# USB-I2C_A2.net
KiCad netlist of a schematic drawn in Altium Designer
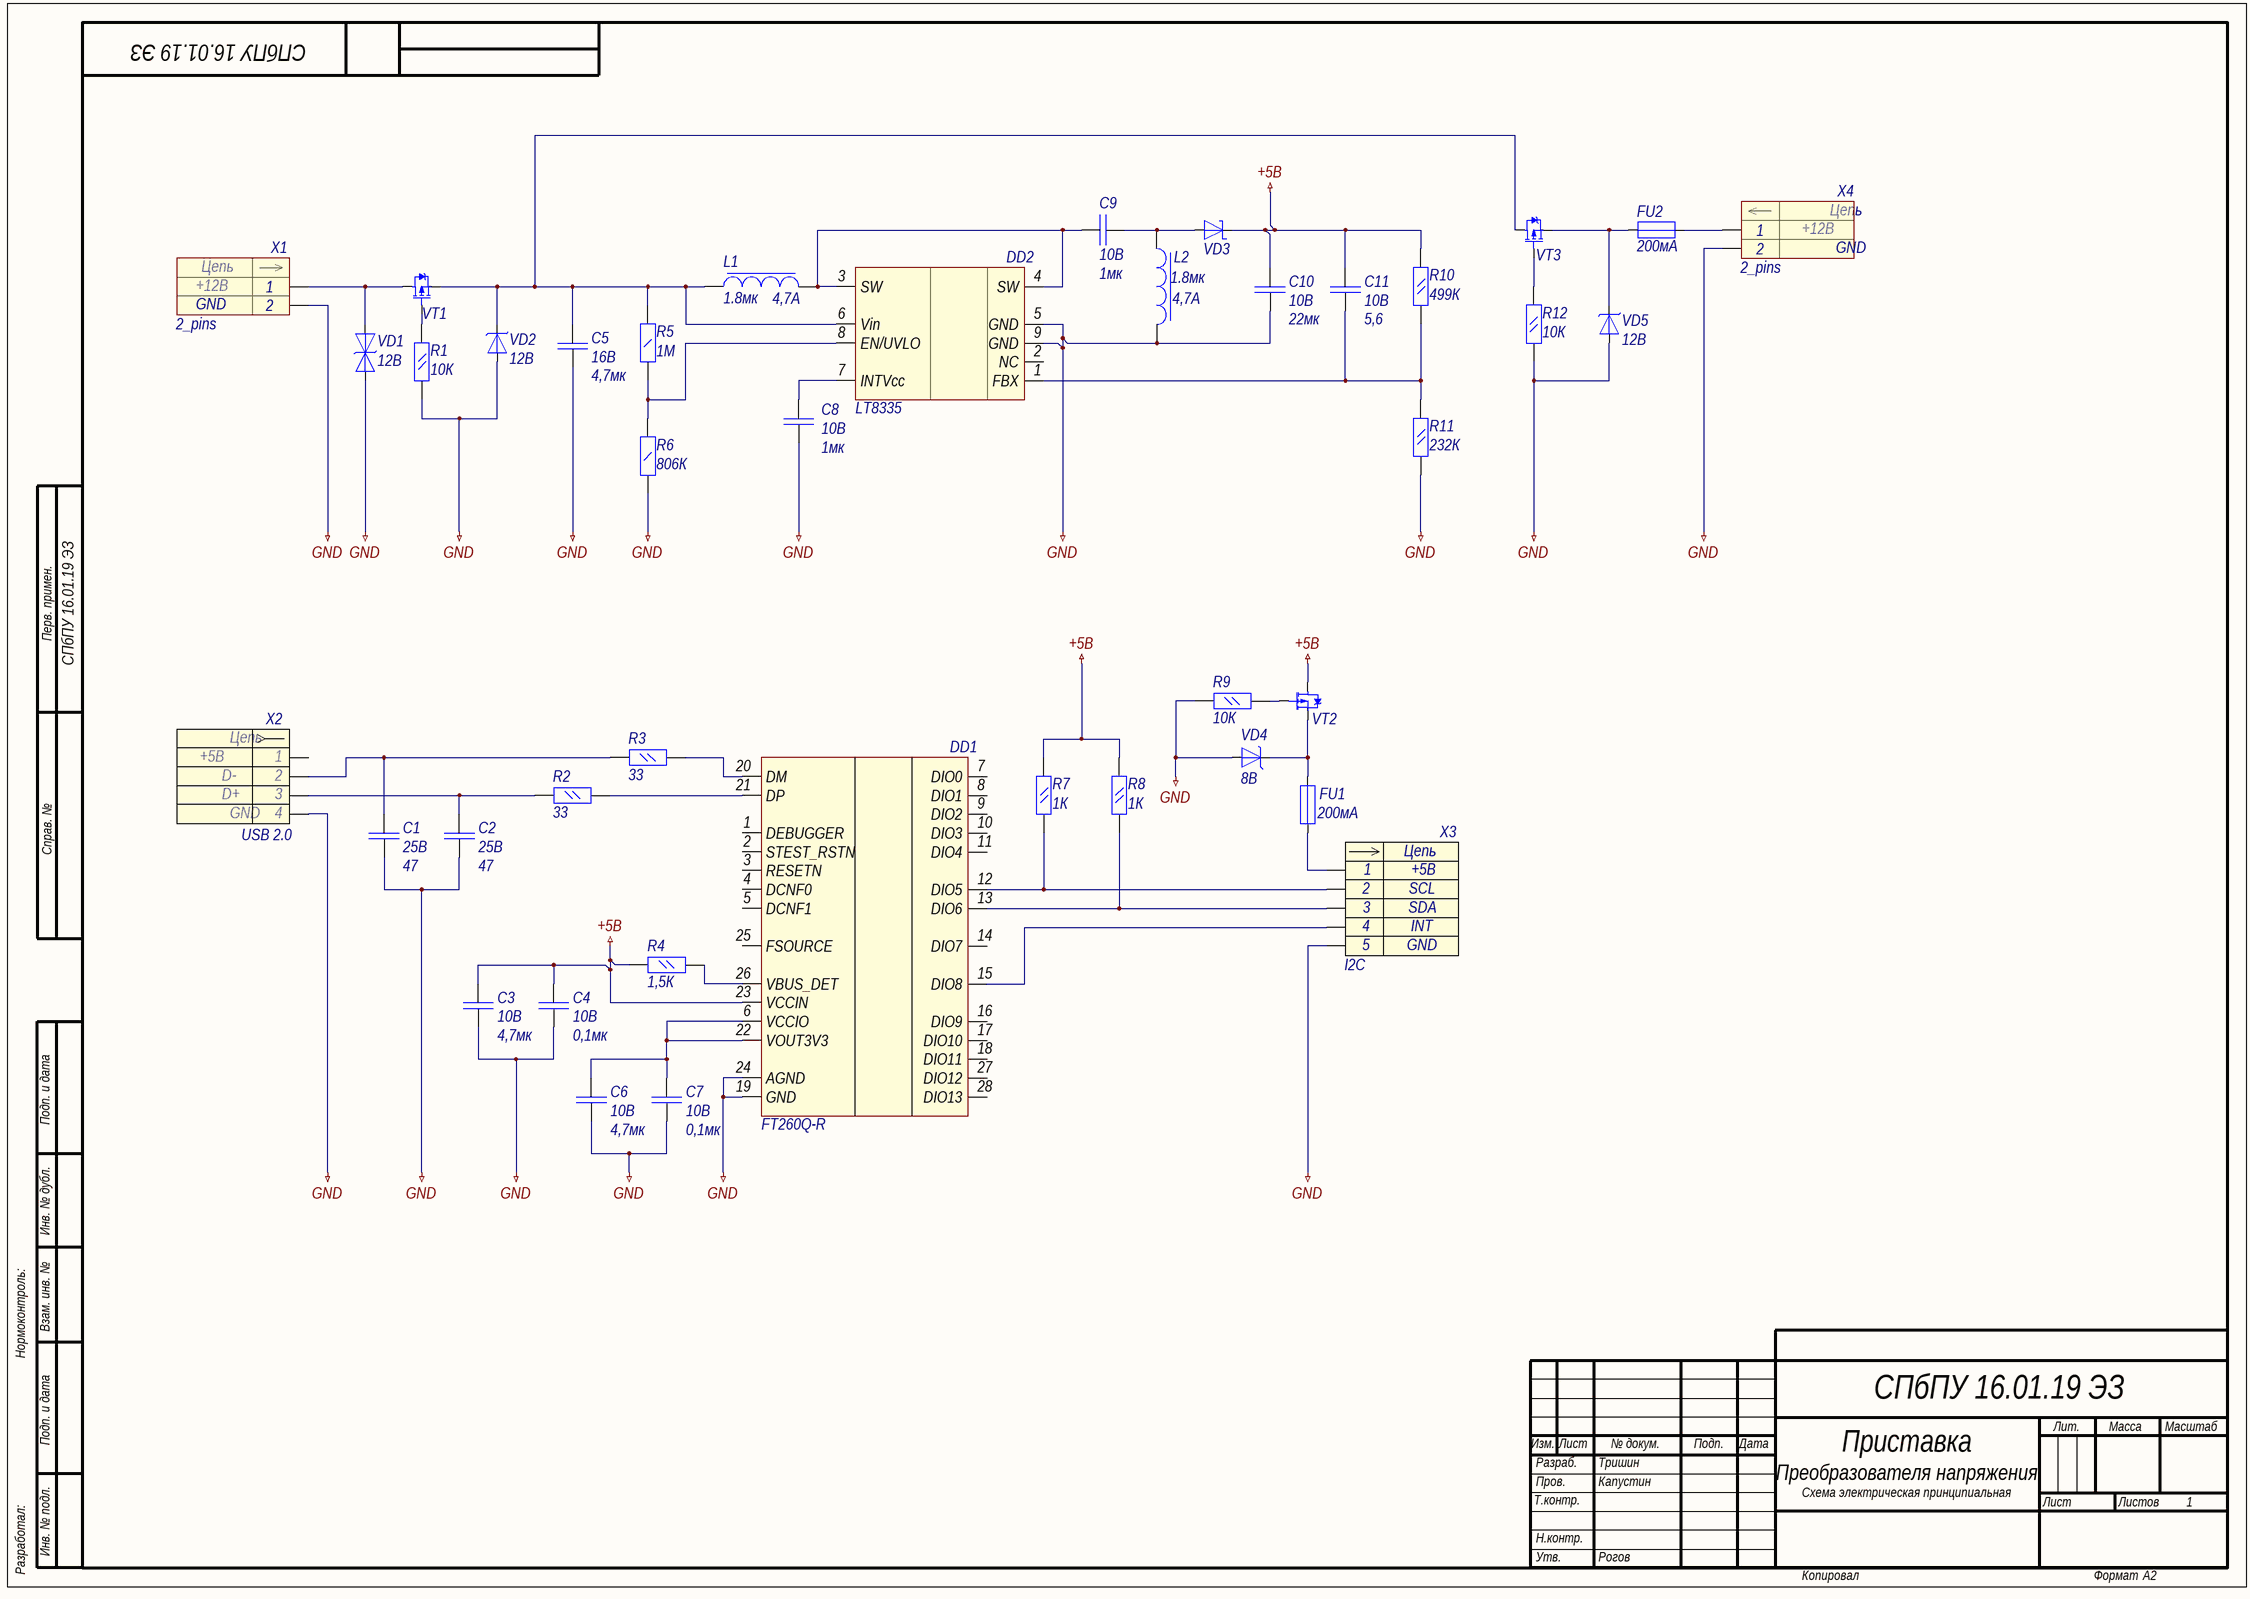
[diagram p0: USB-I2C_A2.SchDoc]

(export (version "E")
  (design (tool "Eeschema 10.0.6"))
  (components
    (comp (ref "C1")
      (value "Capacitor")
      (footprint "CH0201C")
      (fields (field (name "VOLTAGE") "25В") (field (name "CAPACITANCE") "47"))
      (libsource (lib "GOST_Capacitors") (part "Capacitor"))
    )
    (comp (ref "C2")
      (value "Capacitor")
      (footprint "CH0201C")
      (fields (field (name "VOLTAGE") "25В") (field (name "CAPACITANCE") "47"))
      (libsource (lib "GOST_Capacitors") (part "Capacitor"))
    )
    (comp (ref "C3")
      (value "Capacitor")
      (footprint "CH0402C")
      (fields (field (name "VOLTAGE") "10В") (field (name "CAPACITANCE") "4,7мк"))
      (libsource (lib "GOST_Capacitors") (part "Capacitor"))
    )
    (comp (ref "C4")
      (value "Capacitor")
      (footprint "CH0402C")
      (fields (field (name "VOLTAGE") "10В") (field (name "CAPACITANCE") "0,1мк"))
      (libsource (lib "GOST_Capacitors") (part "Capacitor"))
    )
    (comp (ref "C5")
      (value "Capacitor")
      (footprint "CH0603C")
      (fields (field (name "VOLTAGE") "16В") (field (name "CAPACITANCE") "4,7мк"))
      (libsource (lib "GOST_Capacitors") (part "Capacitor"))
    )
    (comp (ref "C6")
      (value "Capacitor")
      (footprint "CH0402C")
      (fields (field (name "VOLTAGE") "10В") (field (name "CAPACITANCE") "4,7мк"))
      (libsource (lib "GOST_Capacitors") (part "Capacitor"))
    )
    (comp (ref "C7")
      (value "Capacitor")
      (footprint "CH0402C")
      (fields (field (name "VOLTAGE") "10В") (field (name "CAPACITANCE") "0,1мк"))
      (libsource (lib "GOST_Capacitors") (part "Capacitor"))
    )
    (comp (ref "C8")
      (value "Capacitor")
      (footprint "CH0201C")
      (fields (field (name "VOLTAGE") "10В") (field (name "CAPACITANCE") "1мк"))
      (libsource (lib "GOST_Capacitors") (part "Capacitor"))
    )
    (comp (ref "C9")
      (value "Capacitor")
      (footprint "CH0201C")
      (fields (field (name "VOLTAGE") "10В") (field (name "CAPACITANCE") "1мк"))
      (libsource (lib "GOST_Capacitors") (part "Capacitor"))
    )
    (comp (ref "C10")
      (value "Capacitor")
      (footprint "CH0603C")
      (fields (field (name "VOLTAGE") "10В") (field (name "CAPACITANCE") "22мк"))
      (libsource (lib "GOST_Capacitors") (part "Capacitor"))
    )
    (comp (ref "C11")
      (value "Capacitor")
      (footprint "CH0201C")
      (fields (field (name "VOLTAGE") "10В") (field (name "CAPACITANCE") "5,6"))
      (libsource (lib "GOST_Capacitors") (part "Capacitor"))
    )
    (comp (ref "DD1")
      (value "FT260Q-R")
      (footprint "FT260-Q")
      (description "IC BRIDGE USB TO UART/I2C 28WQFN")
      (libsource (lib "GOST_lib_devices") (part "FT260Q-R"))
    )
    (comp (ref "DD2")
      (value "LT8335")
      (footprint "LT8335")
      (description "4~16 to 5")
      (libsource (lib "GOST_lib_devices") (part "LT8335"))
    )
    (comp (ref "FU1")
      (value "200мА")
      (footprint "CH0402R")
      (fields (field (name "Comment") "Fuse"))
      (libsource (lib "GOST_Miscelanuious") (part "Fuse"))
    )
    (comp (ref "FU2")
      (value "200мА")
      (footprint "CH0402R")
      (fields (field (name "Comment") "Fuse"))
      (libsource (lib "") (part "Fuse_1"))
    )
    (comp (ref "L1")
      (value "Ferrite bead")
      (footprint "IND: DRQ127")
      (fields (field (name "MAX DC CURRENT") "4,7А") (field (name "INDUCTANCE") "1.8мк"))
      (libsource (lib "GOST_Inductors") (part "Ferrite bead"))
    )
    (comp (ref "L2")
      (value "Ferrite bead")
      (footprint "IND: DRQ127")
      (fields (field (name "MAX DC CURRENT") "4,7А") (field (name "INDUCTANCE") "1.8мк"))
      (libsource (lib "GOST_Inductors") (part "Ferrite bead"))
    )
    (comp (ref "R1")
      (value "Res_0.125")
      (footprint "CH0402R")
      (fields (field (name "IMPEDANCE") "10К"))
      (libsource (lib "GOST_Resistors") (part "Res_0.125"))
    )
    (comp (ref "R2")
      (value "Res_0.125")
      (footprint "CH0402R")
      (fields (field (name "IMPEDANCE") "33"))
      (libsource (lib "GOST_Resistors") (part "Res_0.125"))
    )
    (comp (ref "R3")
      (value "Res_0.125")
      (footprint "CH0402R")
      (fields (field (name "IMPEDANCE") "33"))
      (libsource (lib "GOST_Resistors") (part "Res_0.125"))
    )
    (comp (ref "R4")
      (value "Res_0.125")
      (footprint "CH0402R")
      (fields (field (name "IMPEDANCE") "1,5К"))
      (libsource (lib "GOST_Resistors") (part "Res_0.125"))
    )
    (comp (ref "R5")
      (value "Res_0.5")
      (footprint "CH0805R")
      (fields (field (name "IMPEDANCE") "1М"))
      (libsource (lib "GOST_Resistors") (part "Res_0.5"))
    )
    (comp (ref "R6")
      (value "Res_0.5")
      (footprint "CH0805R")
      (fields (field (name "IMPEDANCE") "806К"))
      (libsource (lib "GOST_Resistors") (part "Res_0.5"))
    )
    (comp (ref "R7")
      (value "Res_0.125")
      (footprint "CH0402R")
      (fields (field (name "IMPEDANCE") "1К"))
      (libsource (lib "GOST_Resistors") (part "Res_0.125"))
    )
    (comp (ref "R8")
      (value "Res_0.125")
      (footprint "CH0402R")
      (fields (field (name "IMPEDANCE") "1К"))
      (libsource (lib "GOST_Resistors") (part "Res_0.125"))
    )
    (comp (ref "R9")
      (value "Res_0.125")
      (footprint "CH0402R")
      (fields (field (name "IMPEDANCE") "10К"))
      (libsource (lib "GOST_Resistors") (part "Res_0.125"))
    )
    (comp (ref "R10")
      (value "Res_0.125")
      (footprint "CH0805R")
      (fields (field (name "IMPEDANCE") "499К"))
      (libsource (lib "GOST_Resistors") (part "Res_0.125"))
    )
    (comp (ref "R11")
      (value "Res_0.125")
      (footprint "CH0805R")
      (fields (field (name "IMPEDANCE") "232К"))
      (libsource (lib "GOST_Resistors") (part "Res_0.125"))
    )
    (comp (ref "R12")
      (value "Res_0.125")
      (footprint "CH0402R")
      (fields (field (name "IMPEDANCE") "10К"))
      (libsource (lib "GOST_Resistors") (part "Res_0.125"))
    )
    (comp (ref "VD1")
      (value "TVS-diod_simmetrical")
      (footprint "CH0201L")
      (fields (field (name "MANUFACTURER") "Littelfuse") (field (name "CLAMPING VOLTAGE") "12В"))
      (libsource (lib "GOST_Diodes") (part "TVS-diod_simmetrical"))
    )
    (comp (ref "VD2")
      (value "TVS-diod_directed")
      (footprint "DO214AA")
      (fields (field (name "MANUFACTURER") "Bourns") (field (name "CLAMPING_VOLTAGE") "12В"))
      (libsource (lib "GOST_Diodes") (part "TVS-diod_directed"))
    )
    (comp (ref "VD3")
      (value "Diod Schottky")
      (footprint "SOT23_132")
      (fields (field (name "MANUFACTURER") "Toshiba"))
      (libsource (lib "GOST_Diodes") (part "Diod Schottky"))
    )
    (comp (ref "VD4")
      (value "TVS-diod_directed")
      (footprint "SOD123W")
      (fields (field (name "MANUFACTURER") "Nexperia") (field (name "CLAMPING_VOLTAGE") "8В"))
      (libsource (lib "GOST_Diodes") (part "TVS-diod_directed"))
    )
    (comp (ref "VD5")
      (value "TVS-diod_directed")
      (footprint "DO214AA")
      (fields (field (name "MANUFACTURER") "Bourns") (field (name "CLAMPING_VOLTAGE") "12В"))
      (libsource (lib "GOST_Diodes") (part "TVS-diod_directed"))
    )
    (comp (ref "VT1")
      (value "*")
      (footprint "SOT23_132")
      (libsource (lib "GOST_Transistors") (part "P-Channel"))
    )
    (comp (ref "VT2")
      (value "*")
      (footprint "SOT23_132")
      (libsource (lib "GOST_Transistors") (part "P-Channel"))
    )
    (comp (ref "VT3")
      (value "*")
      (footprint "SOT23_132")
      (libsource (lib "GOST_Transistors") (part "P-Channel"))
    )
    (comp (ref "X1")
      (value "2_pins")
      (footprint "CON: 163-179PH-EX")
      (fields (field (name "VCC") "+12В"))
      (libsource (lib "GOST_lib_connectors") (part "2_pins"))
    )
    (comp (ref "X2")
      (value "USB 2.0")
      (footprint "Integrated_Library:USB")
      (description "USB")
      (fields (field (name "MANUFACTURER") "TE Connectivity") (field (name "VCC") "+5В"))
      (libsource (lib "Connectors") (part "USB-A"))
    )
    (comp (ref "X3")
      (value "I2C")
      (footprint "CON: PBS-5")
      (description "Разъем - 5 конт. вилка")
      (libsource (lib "MOP44") (part "Header_5_plg"))
    )
    (comp (ref "X4")
      (value "2_pins")
      (footprint "CON: PBS-2")
      (fields (field (name "VCC") "+12В"))
      (libsource (lib "") (part "2_pins_1"))
    )
  )
  (nets
    (net (code "1") (name "+5В") (class "Default")
      (node (ref "C10") (pin "1") (pinfunction "C1+_1") (pintype "power_in"))
      (node (ref "C11") (pin "1") (pinfunction "C1+_1") (pintype "power_in"))
      (node (ref "C3") (pin "1") (pinfunction "C1+_1") (pintype "power_in"))
      (node (ref "C4") (pin "1") (pinfunction "C1+_1") (pintype "power_in"))
      (node (ref "DD1") (pin "23") (pinfunction "VCCIN_23") (pintype "passive"))
      (node (ref "R10") (pin "1") (pinfunction "C1-_1") (pintype "power_in"))
      (node (ref "R4") (pin "2") (pinfunction "C1-_2") (pintype "power_in"))
      (node (ref "R7") (pin "1") (pinfunction "C1-_1") (pintype "power_in"))
      (node (ref "R8") (pin "1") (pinfunction "C1-_1") (pintype "power_in"))
      (node (ref "VD3") (pin "2") (pinfunction "2_2") (pintype "passive"))
      (node (ref "VT2") (pin "2") (pinfunction "D_2") (pintype "passive"))
    )
    (net (code "2") (name "GND") (class "Default")
      (node (ref "C1") (pin "2") (pinfunction "C1-_2") (pintype "power_in"))
      (node (ref "C10") (pin "2") (pinfunction "C1-_2") (pintype "power_in"))
      (node (ref "C2") (pin "2") (pinfunction "C1-_2") (pintype "power_in"))
      (node (ref "C3") (pin "2") (pinfunction "C1-_2") (pintype "power_in"))
      (node (ref "C4") (pin "2") (pinfunction "C1-_2") (pintype "power_in"))
      (node (ref "C5") (pin "2") (pinfunction "C1-_2") (pintype "power_in"))
      (node (ref "C6") (pin "2") (pinfunction "C1-_2") (pintype "power_in"))
      (node (ref "C7") (pin "2") (pinfunction "C1-_2") (pintype "power_in"))
      (node (ref "C8") (pin "2") (pinfunction "C1-_2") (pintype "power_in"))
      (node (ref "DD1") (pin "19") (pinfunction "GND_19") (pintype "passive"))
      (node (ref "DD1") (pin "24") (pinfunction "AGND_24") (pintype "passive"))
      (node (ref "DD2") (pin "5") (pinfunction "GND_5") (pintype "power_in"))
      (node (ref "DD2") (pin "9") (pinfunction "GND_9") (pintype "power_in"))
      (node (ref "L2") (pin "2") (pinfunction "14_2") (pintype "power_in"))
      (node (ref "R1") (pin "2") (pinfunction "C1-_2") (pintype "power_in"))
      (node (ref "R11") (pin "2") (pinfunction "C1-_2") (pintype "power_in"))
      (node (ref "R12") (pin "1") (pinfunction "C1-_1") (pintype "power_in"))
      (node (ref "R6") (pin "1") (pinfunction "C1-_1") (pintype "power_in"))
      (node (ref "R9") (pin "2") (pinfunction "C1-_2") (pintype "power_in"))
      (node (ref "VD1") (pin "1") (pinfunction "A_1") (pintype "passive"))
      (node (ref "VD2") (pin "1") (pinfunction "A_1") (pintype "passive"))
      (node (ref "VD4") (pin "1") (pinfunction "A_1") (pintype "passive"))
      (node (ref "VD5") (pin "1") (pinfunction "A_1") (pintype "passive"))
      (node (ref "X1") (pin "2") (pinfunction "2_2") (pintype "passive"))
      (node (ref "X2") (pin "4") (pinfunction "4_4") (pintype "passive"))
      (node (ref "X3") (pin "5") (pinfunction "5_5") (pintype "passive"))
      (node (ref "X4") (pin "2") (pinfunction "2_2") (pintype "passive"))
    )
    (net (code "3") (name "Net-(C1-C1+)") (class "Default")
      (node (ref "C1") (pin "1") (pinfunction "C1+_1") (pintype "power_in"))
      (node (ref "R3") (pin "2") (pinfunction "C1-_2") (pintype "power_in"))
      (node (ref "X2") (pin "2") (pinfunction "2_2") (pintype "passive"))
    )
    (net (code "4") (name "Net-(C2-C1+)") (class "Default")
      (node (ref "C2") (pin "1") (pinfunction "C1+_1") (pintype "power_in"))
      (node (ref "R2") (pin "2") (pinfunction "C1-_2") (pintype "power_in"))
      (node (ref "X2") (pin "3") (pinfunction "3_3") (pintype "passive"))
    )
    (net (code "5") (name "Net-(C5-C1+)") (class "Default")
      (node (ref "C5") (pin "1") (pinfunction "C1+_1") (pintype "power_in"))
      (node (ref "DD2") (pin "6") (pinfunction "Vin_6") (pintype "power_in"))
      (node (ref "L1") (pin "1") (pinfunction "C1-_1") (pintype "power_in"))
      (node (ref "R5") (pin "2") (pinfunction "C1-_2") (pintype "power_in"))
      (node (ref "VD2") (pin "2") (pinfunction "C_2") (pintype "passive"))
      (node (ref "VT1") (pin "3") (pinfunction "S_3") (pintype "passive"))
      (node (ref "VT3") (pin "2") (pinfunction "D_2") (pintype "passive"))
    )
    (net (code "6") (name "Net-(C6-C1+)") (class "Default")
      (node (ref "C6") (pin "1") (pinfunction "C1+_1") (pintype "power_in"))
      (node (ref "C7") (pin "1") (pinfunction "C1+_1") (pintype "power_in"))
      (node (ref "DD1") (pin "22") (pinfunction "VOUT3V3_22") (pintype "passive"))
      (node (ref "DD1") (pin "6") (pinfunction "VCCIO_6") (pintype "passive"))
    )
    (net (code "7") (name "Net-(C8-C1+)") (class "Default")
      (node (ref "C8") (pin "1") (pinfunction "C1+_1") (pintype "power_in"))
      (node (ref "DD2") (pin "7") (pinfunction "INTVcc_7") (pintype "power_in"))
    )
    (net (code "8") (name "Net-(C9-C1+)") (class "Default")
      (node (ref "C9") (pin "1") (pinfunction "C1+_1") (pintype "power_in"))
      (node (ref "DD2") (pin "3") (pinfunction "SW_3") (pintype "power_in"))
      (node (ref "DD2") (pin "4") (pinfunction "SW_4") (pintype "power_in"))
      (node (ref "L1") (pin "2") (pinfunction "14_2") (pintype "power_in"))
    )
    (net (code "9") (name "Net-(C9-C1-)") (class "Default")
      (node (ref "C9") (pin "2") (pinfunction "C1-_2") (pintype "power_in"))
      (node (ref "L2") (pin "1") (pinfunction "C1-_1") (pintype "power_in"))
      (node (ref "VD3") (pin "1") (pinfunction "1_1") (pintype "passive"))
    )
    (net (code "10") (name "Net-(C11-C1-)") (class "Default")
      (node (ref "C11") (pin "2") (pinfunction "C1-_2") (pintype "power_in"))
      (node (ref "DD2") (pin "1") (pinfunction "FBX_1") (pintype "power_in"))
      (node (ref "R10") (pin "2") (pinfunction "C1-_2") (pintype "power_in"))
      (node (ref "R11") (pin "1") (pinfunction "C1-_1") (pintype "power_in"))
    )
    (net (code "11") (name "Net-(DD1-DIO5)") (class "Default")
      (node (ref "DD1") (pin "12") (pinfunction "DIO5_12") (pintype "passive"))
      (node (ref "R7") (pin "2") (pinfunction "C1-_2") (pintype "power_in"))
      (node (ref "X3") (pin "2") (pinfunction "2_2") (pintype "passive"))
    )
    (net (code "12") (name "Net-(DD1-DIO6)") (class "Default")
      (node (ref "DD1") (pin "13") (pinfunction "DIO6_13") (pintype "passive"))
      (node (ref "R8") (pin "2") (pinfunction "C1-_2") (pintype "power_in"))
      (node (ref "X3") (pin "3") (pinfunction "3_3") (pintype "passive"))
    )
    (net (code "13") (name "Net-(DD1-DIO8)") (class "Default")
      (node (ref "DD1") (pin "15") (pinfunction "DIO8_15") (pintype "passive"))
      (node (ref "X3") (pin "4") (pinfunction "4_4") (pintype "passive"))
    )
    (net (code "14") (name "Net-(DD1-DM)") (class "Default")
      (node (ref "DD1") (pin "20") (pinfunction "DM_20") (pintype "passive"))
      (node (ref "R3") (pin "1") (pinfunction "C1-_1") (pintype "power_in"))
    )
    (net (code "15") (name "Net-(DD1-DP)") (class "Default")
      (node (ref "DD1") (pin "21") (pinfunction "DP_21") (pintype "passive"))
      (node (ref "R2") (pin "1") (pinfunction "C1-_1") (pintype "power_in"))
    )
    (net (code "16") (name "Net-(DD1-VBUS_DET)") (class "Default")
      (node (ref "DD1") (pin "26") (pinfunction "VBUS_DET_26") (pintype "passive"))
      (node (ref "R4") (pin "1") (pinfunction "C1-_1") (pintype "power_in"))
    )
    (net (code "17") (name "Net-(DD2-EN{slash}UVLO)") (class "Default")
      (node (ref "DD2") (pin "8") (pinfunction "EN/UVLO_8") (pintype "power_in"))
      (node (ref "R5") (pin "1") (pinfunction "C1-_1") (pintype "power_in"))
      (node (ref "R6") (pin "2") (pinfunction "C1-_2") (pintype "power_in"))
    )
    (net (code "18") (name "Net-(FU1-Pad1)") (class "Default")
      (node (ref "FU1") (pin "1") (pinfunction "1_1") (pintype "passive"))
      (node (ref "X3") (pin "1") (pinfunction "1_1") (pintype "passive"))
    )
    (net (code "19") (name "Net-(FU2-Pad2)") (class "Default")
      (node (ref "FU2") (pin "2") (pinfunction "2_2") (pintype "passive"))
      (node (ref "X4") (pin "1") (pinfunction "1_1") (pintype "passive"))
    )
    (net (code "20") (name "Net-(VD1-C)") (class "Default")
      (node (ref "VD1") (pin "2") (pinfunction "C_2") (pintype "passive"))
      (node (ref "VT1") (pin "2") (pinfunction "D_2") (pintype "passive"))
      (node (ref "X1") (pin "1") (pinfunction "1_1") (pintype "passive"))
    )
    (net (code "21") (name "Net-(VD4-C)") (class "Default")
      (node (ref "FU1") (pin "2") (pinfunction "2_2") (pintype "passive"))
      (node (ref "VD4") (pin "2") (pinfunction "C_2") (pintype "passive"))
      (node (ref "VT2") (pin "3") (pinfunction "S_3") (pintype "passive"))
    )
    (net (code "22") (name "Net-(VD5-C)") (class "Default")
      (node (ref "FU2") (pin "1") (pinfunction "1_1") (pintype "passive"))
      (node (ref "VD5") (pin "2") (pinfunction "C_2") (pintype "passive"))
      (node (ref "VT3") (pin "3") (pinfunction "S_3") (pintype "passive"))
    )
    (net (code "23") (name "Net-(VT1-G)") (class "Default")
      (node (ref "R1") (pin "1") (pinfunction "C1-_1") (pintype "power_in"))
      (node (ref "VT1") (pin "1") (pinfunction "G_1") (pintype "passive"))
    )
    (net (code "24") (name "Net-(VT2-G)") (class "Default")
      (node (ref "R9") (pin "1") (pinfunction "C1-_1") (pintype "power_in"))
      (node (ref "VT2") (pin "1") (pinfunction "G_1") (pintype "passive"))
    )
    (net (code "25") (name "Net-(VT3-G)") (class "Default")
      (node (ref "R12") (pin "2") (pinfunction "C1-_2") (pintype "power_in"))
      (node (ref "VT3") (pin "1") (pinfunction "G_1") (pintype "passive"))
    )
    (net (code "26") (name "unconnected-(DD1-DCNF0-Pad4)") (class "Default")
      (node (ref "DD1") (pin "4") (pinfunction "DCNF0_4") (pintype "passive"))
    )
    (net (code "27") (name "unconnected-(DD1-DCNF1-Pad5)") (class "Default")
      (node (ref "DD1") (pin "5") (pinfunction "DCNF1_5") (pintype "passive"))
    )
    (net (code "28") (name "unconnected-(DD1-DEBUGGER-Pad1)") (class "Default")
      (node (ref "DD1") (pin "1") (pinfunction "DEBUGGER_1") (pintype "passive"))
    )
    (net (code "29") (name "unconnected-(DD1-DIO0-Pad7)") (class "Default")
      (node (ref "DD1") (pin "7") (pinfunction "DIO0_7") (pintype "passive"))
    )
    (net (code "30") (name "unconnected-(DD1-DIO1-Pad8)") (class "Default")
      (node (ref "DD1") (pin "8") (pinfunction "DIO1_8") (pintype "passive"))
    )
    (net (code "31") (name "unconnected-(DD1-DIO2-Pad9)") (class "Default")
      (node (ref "DD1") (pin "9") (pinfunction "DIO2_9") (pintype "passive"))
    )
    (net (code "32") (name "unconnected-(DD1-DIO3-Pad10)") (class "Default")
      (node (ref "DD1") (pin "10") (pinfunction "DIO3_10") (pintype "passive"))
    )
    (net (code "33") (name "unconnected-(DD1-DIO4-Pad11)") (class "Default")
      (node (ref "DD1") (pin "11") (pinfunction "DIO4_11") (pintype "passive"))
    )
    (net (code "34") (name "unconnected-(DD1-DIO7-Pad14)") (class "Default")
      (node (ref "DD1") (pin "14") (pinfunction "DIO7_14") (pintype "passive"))
    )
    (net (code "35") (name "unconnected-(DD1-DIO9-Pad16)") (class "Default")
      (node (ref "DD1") (pin "16") (pinfunction "DIO9_16") (pintype "passive"))
    )
    (net (code "36") (name "unconnected-(DD1-DIO10-Pad17)") (class "Default")
      (node (ref "DD1") (pin "17") (pinfunction "DIO10_17") (pintype "passive"))
    )
    (net (code "37") (name "unconnected-(DD1-DIO11-Pad18)") (class "Default")
      (node (ref "DD1") (pin "18") (pinfunction "DIO11_18") (pintype "passive"))
    )
    (net (code "38") (name "unconnected-(DD1-DIO12-Pad27)") (class "Default")
      (node (ref "DD1") (pin "27") (pinfunction "DIO12_27") (pintype "passive"))
    )
    (net (code "39") (name "unconnected-(DD1-DIO13-Pad28)") (class "Default")
      (node (ref "DD1") (pin "28") (pinfunction "DIO13_28") (pintype "passive"))
    )
    (net (code "40") (name "unconnected-(DD1-FSOURCE-Pad25)") (class "Default")
      (node (ref "DD1") (pin "25") (pinfunction "FSOURCE_25") (pintype "passive"))
    )
    (net (code "41") (name "unconnected-(DD1-RESETN-Pad3)") (class "Default")
      (node (ref "DD1") (pin "3") (pinfunction "RESETN_3") (pintype "passive"))
    )
    (net (code "42") (name "unconnected-(DD1-STEST_RSTN-Pad2)") (class "Default")
      (node (ref "DD1") (pin "2") (pinfunction "STEST_RSTN_2") (pintype "passive"))
    )
    (net (code "43") (name "unconnected-(DD2-NC-Pad2)") (class "Default")
      (node (ref "DD2") (pin "2") (pinfunction "NC_2") (pintype "power_in"))
    )
    (net (code "44") (name "unconnected-(X2-Pad1)") (class "Default")
      (node (ref "X2") (pin "1") (pintype "passive"))
    )
  )
)
